# FPGA_Power.net
KiCad netlist of a schematic drawn in Altium Designer
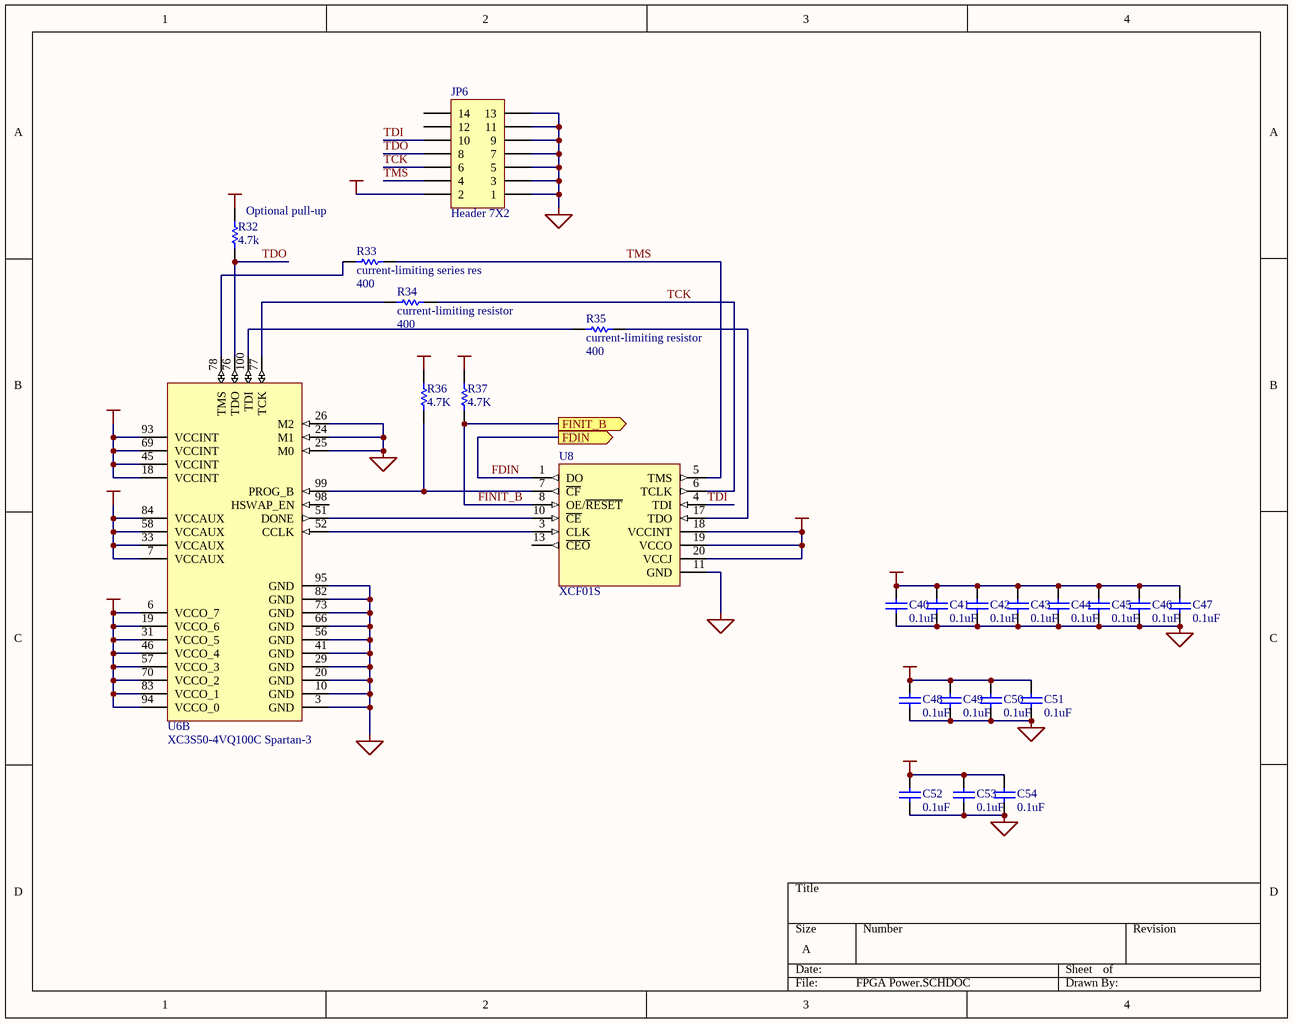
[diagram p0: FPGA Power.SCHDOC]

(export (version "E")
  (design (tool "Eeschema 10.0.6"))
  (components
    (comp (ref "C40")
      (value "0.1uF")
      (footprint "CC1608-0603")
      (description "Capacitor")
      (fields
        (field (name "MANUFACTURER") "Generic Components")
        (field (name "Comment") "Cap")
        (field (name "PUBLISHER") "Altium Limited")
      )
      (libsource (lib "Miscellaneous Devices") (part "Cap"))
    )
    (comp (ref "C41")
      (value "0.1uF")
      (footprint "CC1608-0603")
      (description "Capacitor")
      (fields
        (field (name "MANUFACTURER") "Generic Components")
        (field (name "Comment") "Cap")
        (field (name "PUBLISHER") "Altium Limited")
      )
      (libsource (lib "Miscellaneous Devices") (part "Cap"))
    )
    (comp (ref "C42")
      (value "0.1uF")
      (footprint "CC1608-0603")
      (description "Capacitor")
      (fields
        (field (name "MANUFACTURER") "Generic Components")
        (field (name "Comment") "Cap")
        (field (name "PUBLISHER") "Altium Limited")
      )
      (libsource (lib "Miscellaneous Devices") (part "Cap"))
    )
    (comp (ref "C43")
      (value "0.1uF")
      (footprint "CC1608-0603")
      (description "Capacitor")
      (fields
        (field (name "MANUFACTURER") "Generic Components")
        (field (name "Comment") "Cap")
        (field (name "PUBLISHER") "Altium Limited")
      )
      (libsource (lib "Miscellaneous Devices") (part "Cap"))
    )
    (comp (ref "C44")
      (value "0.1uF")
      (footprint "CC1608-0603")
      (description "Capacitor")
      (fields
        (field (name "MANUFACTURER") "Generic Components")
        (field (name "Comment") "Cap")
        (field (name "PUBLISHER") "Altium Limited")
      )
      (libsource (lib "Miscellaneous Devices") (part "Cap"))
    )
    (comp (ref "C45")
      (value "0.1uF")
      (footprint "CC1608-0603")
      (description "Capacitor")
      (fields
        (field (name "MANUFACTURER") "Generic Components")
        (field (name "Comment") "Cap")
        (field (name "PUBLISHER") "Altium Limited")
      )
      (libsource (lib "Miscellaneous Devices") (part "Cap"))
    )
    (comp (ref "C46")
      (value "0.1uF")
      (footprint "CC1608-0603")
      (description "Capacitor")
      (fields
        (field (name "MANUFACTURER") "Generic Components")
        (field (name "Comment") "Cap")
        (field (name "PUBLISHER") "Altium Limited")
      )
      (libsource (lib "Miscellaneous Devices") (part "Cap"))
    )
    (comp (ref "C47")
      (value "0.1uF")
      (footprint "CC1608-0603")
      (description "Capacitor")
      (fields
        (field (name "MANUFACTURER") "Generic Components")
        (field (name "Comment") "Cap")
        (field (name "PUBLISHER") "Altium Limited")
      )
      (libsource (lib "Miscellaneous Devices") (part "Cap"))
    )
    (comp (ref "C48")
      (value "0.1uF")
      (footprint "CC1608-0603")
      (description "Capacitor")
      (fields
        (field (name "MANUFACTURER") "Generic Components")
        (field (name "Comment") "Cap")
        (field (name "PUBLISHER") "Altium Limited")
      )
      (libsource (lib "Miscellaneous Devices") (part "Cap"))
    )
    (comp (ref "C49")
      (value "0.1uF")
      (footprint "CC1608-0603")
      (description "Capacitor")
      (fields
        (field (name "MANUFACTURER") "Generic Components")
        (field (name "Comment") "Cap")
        (field (name "PUBLISHER") "Altium Limited")
      )
      (libsource (lib "Miscellaneous Devices") (part "Cap"))
    )
    (comp (ref "C50")
      (value "0.1uF")
      (footprint "CC1608-0603")
      (description "Capacitor")
      (fields
        (field (name "MANUFACTURER") "Generic Components")
        (field (name "Comment") "Cap")
        (field (name "PUBLISHER") "Altium Limited")
      )
      (libsource (lib "Miscellaneous Devices") (part "Cap"))
    )
    (comp (ref "C51")
      (value "0.1uF")
      (footprint "CC1608-0603")
      (description "Capacitor")
      (fields
        (field (name "MANUFACTURER") "Generic Components")
        (field (name "Comment") "Cap")
        (field (name "PUBLISHER") "Altium Limited")
      )
      (libsource (lib "Miscellaneous Devices") (part "Cap"))
    )
    (comp (ref "C52")
      (value "0.1uF")
      (footprint "CC1608-0603")
      (description "Capacitor")
      (fields
        (field (name "MANUFACTURER") "Generic Components")
        (field (name "Comment") "Cap")
        (field (name "PUBLISHER") "Altium Limited")
      )
      (libsource (lib "Miscellaneous Devices") (part "Cap"))
    )
    (comp (ref "C53")
      (value "0.1uF")
      (footprint "CC1608-0603")
      (description "Capacitor")
      (fields
        (field (name "MANUFACTURER") "Generic Components")
        (field (name "Comment") "Cap")
        (field (name "PUBLISHER") "Altium Limited")
      )
      (libsource (lib "Miscellaneous Devices") (part "Cap"))
    )
    (comp (ref "C54")
      (value "0.1uF")
      (footprint "CC1608-0603")
      (description "Capacitor")
      (fields
        (field (name "MANUFACTURER") "Generic Components")
        (field (name "Comment") "Cap")
        (field (name "PUBLISHER") "Altium Limited")
      )
      (libsource (lib "Miscellaneous Devices") (part "Cap"))
    )
    (comp (ref "JP6")
      (value "Header 7X2")
      (footprint "HDR2x7-2mm")
      (description "Header, 7-Pin, Dual row")
      (fields (field (name "MANUFACTURER") "Generic Components") (field (name "PUBLISHER") "Altium Limited"))
      (libsource (lib "Miscellaneous Connectors") (part "Header 7X2"))
    )
    (comp (ref "R32")
      (value "Optional pull-up")
      (footprint "CC1608-0603")
      (description "Resistor")
      (fields
        (field (name "MANUFACTURER") "Generic Components")
        (field (name "ALTIUM_VALUE") "4.7k")
        (field (name "PUBLISHER") "Altium Limited")
      )
      (libsource (lib "Miscellaneous Devices") (part "Res1"))
    )
    (comp (ref "R33")
      (value "current-limiting series res")
      (footprint "CC1608-0603")
      (description "Resistor")
      (fields
        (field (name "MANUFACTURER") "Generic Components")
        (field (name "ALTIUM_VALUE") "400")
        (field (name "PUBLISHER") "Altium Limited")
      )
      (libsource (lib "Miscellaneous Devices") (part "Res1"))
    )
    (comp (ref "R34")
      (value "current-limiting resistor")
      (footprint "CC1608-0603")
      (description "Resistor")
      (fields
        (field (name "MANUFACTURER") "Generic Components")
        (field (name "ALTIUM_VALUE") "400")
        (field (name "PUBLISHER") "Altium Limited")
      )
      (libsource (lib "Miscellaneous Devices") (part "Res1"))
    )
    (comp (ref "R35")
      (value "current-limiting resistor")
      (footprint "CC1608-0603")
      (description "Resistor")
      (fields
        (field (name "MANUFACTURER") "Generic Components")
        (field (name "ALTIUM_VALUE") "400")
        (field (name "PUBLISHER") "Altium Limited")
      )
      (libsource (lib "Miscellaneous Devices") (part "Res1"))
    )
    (comp (ref "R36")
      (value "4.7K")
      (footprint "CC1608-0603")
      (description "Resistor")
      (fields
        (field (name "MANUFACTURER") "Generic Components")
        (field (name "Comment") "Res1")
        (field (name "PUBLISHER") "Altium Limited")
      )
      (libsource (lib "Miscellaneous Devices") (part "Res1"))
    )
    (comp (ref "R37")
      (value "4.7K")
      (footprint "CC1608-0603")
      (description "Resistor")
      (fields
        (field (name "MANUFACTURER") "Generic Components")
        (field (name "Comment") "Res1")
        (field (name "PUBLISHER") "Altium Limited")
      )
      (libsource (lib "Miscellaneous Devices") (part "Res1"))
    )
    (comp (ref "U6")
      (value "XC3S50-4VQ100C Spartan-3")
      (footprint "Xilinx TQ100")
      (description "Xilinx Spartan-3 VQ100")
      (libsource (lib "parts") (part "XC3S50-4VQ100C"))
    )
    (comp (ref "U8")
      (value "XCF01S")
      (footprint "TSSO6x6-G20/X.3")
      (description "Xilinx Platform Flash")
      (libsource (lib "parts") (part "XCF01S"))
    )
  )
  (nets
    (net (code "1") (name "+1.2VCC") (class "Default")
      (node (ref "C48") (pin "1") (pinfunction "1_1") (pintype "passive"))
      (node (ref "C49") (pin "1") (pinfunction "1_1") (pintype "passive"))
      (node (ref "C50") (pin "1") (pinfunction "1_1") (pintype "passive"))
      (node (ref "C51") (pin "1") (pinfunction "1_1") (pintype "passive"))
      (node (ref "U6") (pin "18") (pinfunction "VCCINT_18") (pintype "power_in"))
      (node (ref "U6") (pin "45") (pinfunction "VCCINT_45") (pintype "power_in"))
      (node (ref "U6") (pin "69") (pinfunction "VCCINT_69") (pintype "power_in"))
      (node (ref "U6") (pin "93") (pinfunction "VCCINT_93") (pintype "power_in"))
    )
    (net (code "2") (name "+2.5VCC") (class "Default")
      (node (ref "C52") (pin "1") (pinfunction "1_1") (pintype "passive"))
      (node (ref "C53") (pin "1") (pinfunction "1_1") (pintype "passive"))
      (node (ref "C54") (pin "1") (pinfunction "1_1") (pintype "passive"))
      (node (ref "U6") (pin "33") (pinfunction "VCCAUX_33") (pintype "power_in"))
      (node (ref "U6") (pin "58") (pinfunction "VCCAUX_58") (pintype "power_in"))
      (node (ref "U6") (pin "7") (pinfunction "VCCAUX_7") (pintype "power_in"))
      (node (ref "U6") (pin "84") (pinfunction "VCCAUX_84") (pintype "power_in"))
    )
    (net (code "3") (name "/FDIN") (class "Default")
      (node (ref "U8") (pin "1") (pinfunction "DO_1") (pintype "output"))
    )
    (net (code "4") (name "/FINIT_B") (class "Default")
      (node (ref "R37") (pin "1") (pinfunction "1_1") (pintype "passive"))
      (node (ref "U8") (pin "8") (pinfunction "OE/~{RESET}_8") (pintype "input"))
    )
    (net (code "5") (name "/TCK") (class "Default")
      (node (ref "JP6") (pin "6") (pinfunction "6_6") (pintype "passive"))
      (node (ref "R34") (pin "1") (pinfunction "1_1") (pintype "passive"))
      (node (ref "U8") (pin "6") (pinfunction "TCLK_6") (pintype "output"))
    )
    (net (code "6") (name "/TDI") (class "Default")
      (node (ref "JP6") (pin "10") (pinfunction "10_10") (pintype "passive"))
      (node (ref "U8") (pin "4") (pinfunction "TDI_4") (pintype "input"))
    )
    (net (code "7") (name "/TDO") (class "Default")
      (node (ref "JP6") (pin "8") (pinfunction "8_8") (pintype "passive"))
      (node (ref "R32") (pin "1") (pinfunction "1_1") (pintype "passive"))
      (node (ref "U6") (pin "76") (pinfunction "TDO_76") (pintype "bidirectional"))
    )
    (net (code "8") (name "/TMS") (class "Default")
      (node (ref "JP6") (pin "4") (pinfunction "4_4") (pintype "passive"))
      (node (ref "R33") (pin "1") (pinfunction "1_1") (pintype "passive"))
      (node (ref "U8") (pin "5") (pinfunction "TMS_5") (pintype "output"))
    )
    (net (code "9") (name "GND") (class "Default")
      (node (ref "C40") (pin "2") (pinfunction "2_2") (pintype "passive"))
      (node (ref "C41") (pin "2") (pinfunction "2_2") (pintype "passive"))
      (node (ref "C42") (pin "2") (pinfunction "2_2") (pintype "passive"))
      (node (ref "C43") (pin "2") (pinfunction "2_2") (pintype "passive"))
      (node (ref "C44") (pin "2") (pinfunction "2_2") (pintype "passive"))
      (node (ref "C45") (pin "2") (pinfunction "2_2") (pintype "passive"))
      (node (ref "C46") (pin "2") (pinfunction "2_2") (pintype "passive"))
      (node (ref "C47") (pin "2") (pinfunction "2_2") (pintype "passive"))
      (node (ref "C48") (pin "2") (pinfunction "2_2") (pintype "passive"))
      (node (ref "C49") (pin "2") (pinfunction "2_2") (pintype "passive"))
      (node (ref "C50") (pin "2") (pinfunction "2_2") (pintype "passive"))
      (node (ref "C51") (pin "2") (pinfunction "2_2") (pintype "passive"))
      (node (ref "C52") (pin "2") (pinfunction "2_2") (pintype "passive"))
      (node (ref "C53") (pin "2") (pinfunction "2_2") (pintype "passive"))
      (node (ref "C54") (pin "2") (pinfunction "2_2") (pintype "passive"))
      (node (ref "JP6") (pin "1") (pinfunction "1_1") (pintype "passive"))
      (node (ref "JP6") (pin "11") (pinfunction "11_11") (pintype "passive"))
      (node (ref "JP6") (pin "13") (pinfunction "13_13") (pintype "passive"))
      (node (ref "JP6") (pin "3") (pinfunction "3_3") (pintype "passive"))
      (node (ref "JP6") (pin "5") (pinfunction "5_5") (pintype "passive"))
      (node (ref "JP6") (pin "7") (pinfunction "7_7") (pintype "passive"))
      (node (ref "JP6") (pin "9") (pinfunction "9_9") (pintype "passive"))
      (node (ref "U6") (pin "10") (pinfunction "GND_10") (pintype "power_in"))
      (node (ref "U6") (pin "20") (pinfunction "GND_20") (pintype "power_in"))
      (node (ref "U6") (pin "24") (pinfunction "M1_24") (pintype "input"))
      (node (ref "U6") (pin "25") (pinfunction "M0_25") (pintype "input"))
      (node (ref "U6") (pin "26") (pinfunction "M2_26") (pintype "input"))
      (node (ref "U6") (pin "29") (pinfunction "GND_29") (pintype "power_in"))
      (node (ref "U6") (pin "3") (pinfunction "GND_3") (pintype "power_in"))
      (node (ref "U6") (pin "41") (pinfunction "GND_41") (pintype "power_in"))
      (node (ref "U6") (pin "56") (pinfunction "GND_56") (pintype "power_in"))
      (node (ref "U6") (pin "66") (pinfunction "GND_66") (pintype "power_in"))
      (node (ref "U6") (pin "73") (pinfunction "GND_73") (pintype "power_in"))
      (node (ref "U6") (pin "82") (pinfunction "GND_82") (pintype "power_in"))
      (node (ref "U6") (pin "95") (pinfunction "GND_95") (pintype "power_in"))
      (node (ref "U8") (pin "11") (pinfunction "GND_11") (pintype "power_in"))
    )
    (net (code "10") (name "Net-(U6B-CCLK)") (class "Default")
      (node (ref "U6") (pin "52") (pinfunction "CCLK_52") (pintype "input"))
      (node (ref "U8") (pin "3") (pinfunction "CLK_3") (pintype "input"))
    )
    (net (code "11") (name "Net-(U6B-DONE)") (class "Default")
      (node (ref "U6") (pin "51") (pinfunction "DONE_51") (pintype "output"))
      (node (ref "U8") (pin "10") (pinfunction "~{CE}_10") (pintype "input"))
    )
    (net (code "12") (name "Net-(U6B-PROG_B)") (class "Default")
      (node (ref "R36") (pin "1") (pinfunction "1_1") (pintype "passive"))
      (node (ref "U6") (pin "99") (pinfunction "PROG_B_99") (pintype "input"))
      (node (ref "U8") (pin "7") (pinfunction "~{CF}_7") (pintype "output"))
    )
    (net (code "13") (name "Net-(U6B-TCK)") (class "Default")
      (node (ref "R34") (pin "2") (pinfunction "2_2") (pintype "passive"))
      (node (ref "U6") (pin "77") (pinfunction "TCK_77") (pintype "bidirectional"))
    )
    (net (code "14") (name "Net-(U6B-TDI)") (class "Default")
      (node (ref "R35") (pin "2") (pinfunction "2_2") (pintype "passive"))
      (node (ref "U6") (pin "100") (pinfunction "TDI_100") (pintype "bidirectional"))
    )
    (net (code "15") (name "Net-(U6B-TMS)") (class "Default")
      (node (ref "R33") (pin "2") (pinfunction "2_2") (pintype "passive"))
      (node (ref "U6") (pin "78") (pinfunction "TMS_78") (pintype "bidirectional"))
    )
    (net (code "16") (name "Net-(U8-TDO)") (class "Default")
      (node (ref "R35") (pin "1") (pinfunction "1_1") (pintype "passive"))
      (node (ref "U8") (pin "17") (pinfunction "TDO_17") (pintype "input"))
    )
    (net (code "17") (name "VCC") (class "Default")
      (node (ref "C40") (pin "1") (pinfunction "1_1") (pintype "passive"))
      (node (ref "C41") (pin "1") (pinfunction "1_1") (pintype "passive"))
      (node (ref "C42") (pin "1") (pinfunction "1_1") (pintype "passive"))
      (node (ref "C43") (pin "1") (pinfunction "1_1") (pintype "passive"))
      (node (ref "C44") (pin "1") (pinfunction "1_1") (pintype "passive"))
      (node (ref "C45") (pin "1") (pinfunction "1_1") (pintype "passive"))
      (node (ref "C46") (pin "1") (pinfunction "1_1") (pintype "passive"))
      (node (ref "C47") (pin "1") (pinfunction "1_1") (pintype "passive"))
      (node (ref "JP6") (pin "2") (pinfunction "2_2") (pintype "passive"))
      (node (ref "R32") (pin "2") (pinfunction "2_2") (pintype "passive"))
      (node (ref "R36") (pin "2") (pinfunction "2_2") (pintype "passive"))
      (node (ref "R37") (pin "2") (pinfunction "2_2") (pintype "passive"))
      (node (ref "U6") (pin "19") (pinfunction "VCCO_6_19") (pintype "power_in"))
      (node (ref "U6") (pin "31") (pinfunction "VCCO_5_31") (pintype "power_in"))
      (node (ref "U6") (pin "46") (pinfunction "VCCO_4_46") (pintype "power_in"))
      (node (ref "U6") (pin "57") (pinfunction "VCCO_3_57") (pintype "power_in"))
      (node (ref "U6") (pin "6") (pinfunction "VCCO_7_6") (pintype "power_in"))
      (node (ref "U6") (pin "70") (pinfunction "VCCO_2_70") (pintype "power_in"))
      (node (ref "U6") (pin "83") (pinfunction "VCCO_1_83") (pintype "power_in"))
      (node (ref "U6") (pin "94") (pinfunction "VCCO_0_94") (pintype "power_in"))
      (node (ref "U8") (pin "18") (pinfunction "VCCINT_18") (pintype "power_in"))
      (node (ref "U8") (pin "19") (pinfunction "VCCO_19") (pintype "power_in"))
      (node (ref "U8") (pin "20") (pinfunction "VCCJ_20") (pintype "power_in"))
    )
    (net (code "18") (name "unconnected-(JP6-Pad12)") (class "Default")
      (node (ref "JP6") (pin "12") (pinfunction "12_12") (pintype "passive"))
    )
    (net (code "19") (name "unconnected-(JP6-Pad14)") (class "Default")
      (node (ref "JP6") (pin "14") (pinfunction "14_14") (pintype "passive"))
    )
    (net (code "20") (name "unconnected-(U6B-HSWAP_EN-Pad98)") (class "Default")
      (node (ref "U6") (pin "98") (pinfunction "HSWAP_EN_98") (pintype "input"))
    )
    (net (code "21") (name "unconnected-(U8-~{CEO}-Pad13)") (class "Default")
      (node (ref "U8") (pin "13") (pinfunction "~{CEO}_13") (pintype "output"))
    )
  )
)
